# design.net
KiCad netlist of a schematic drawn in Altium Designer
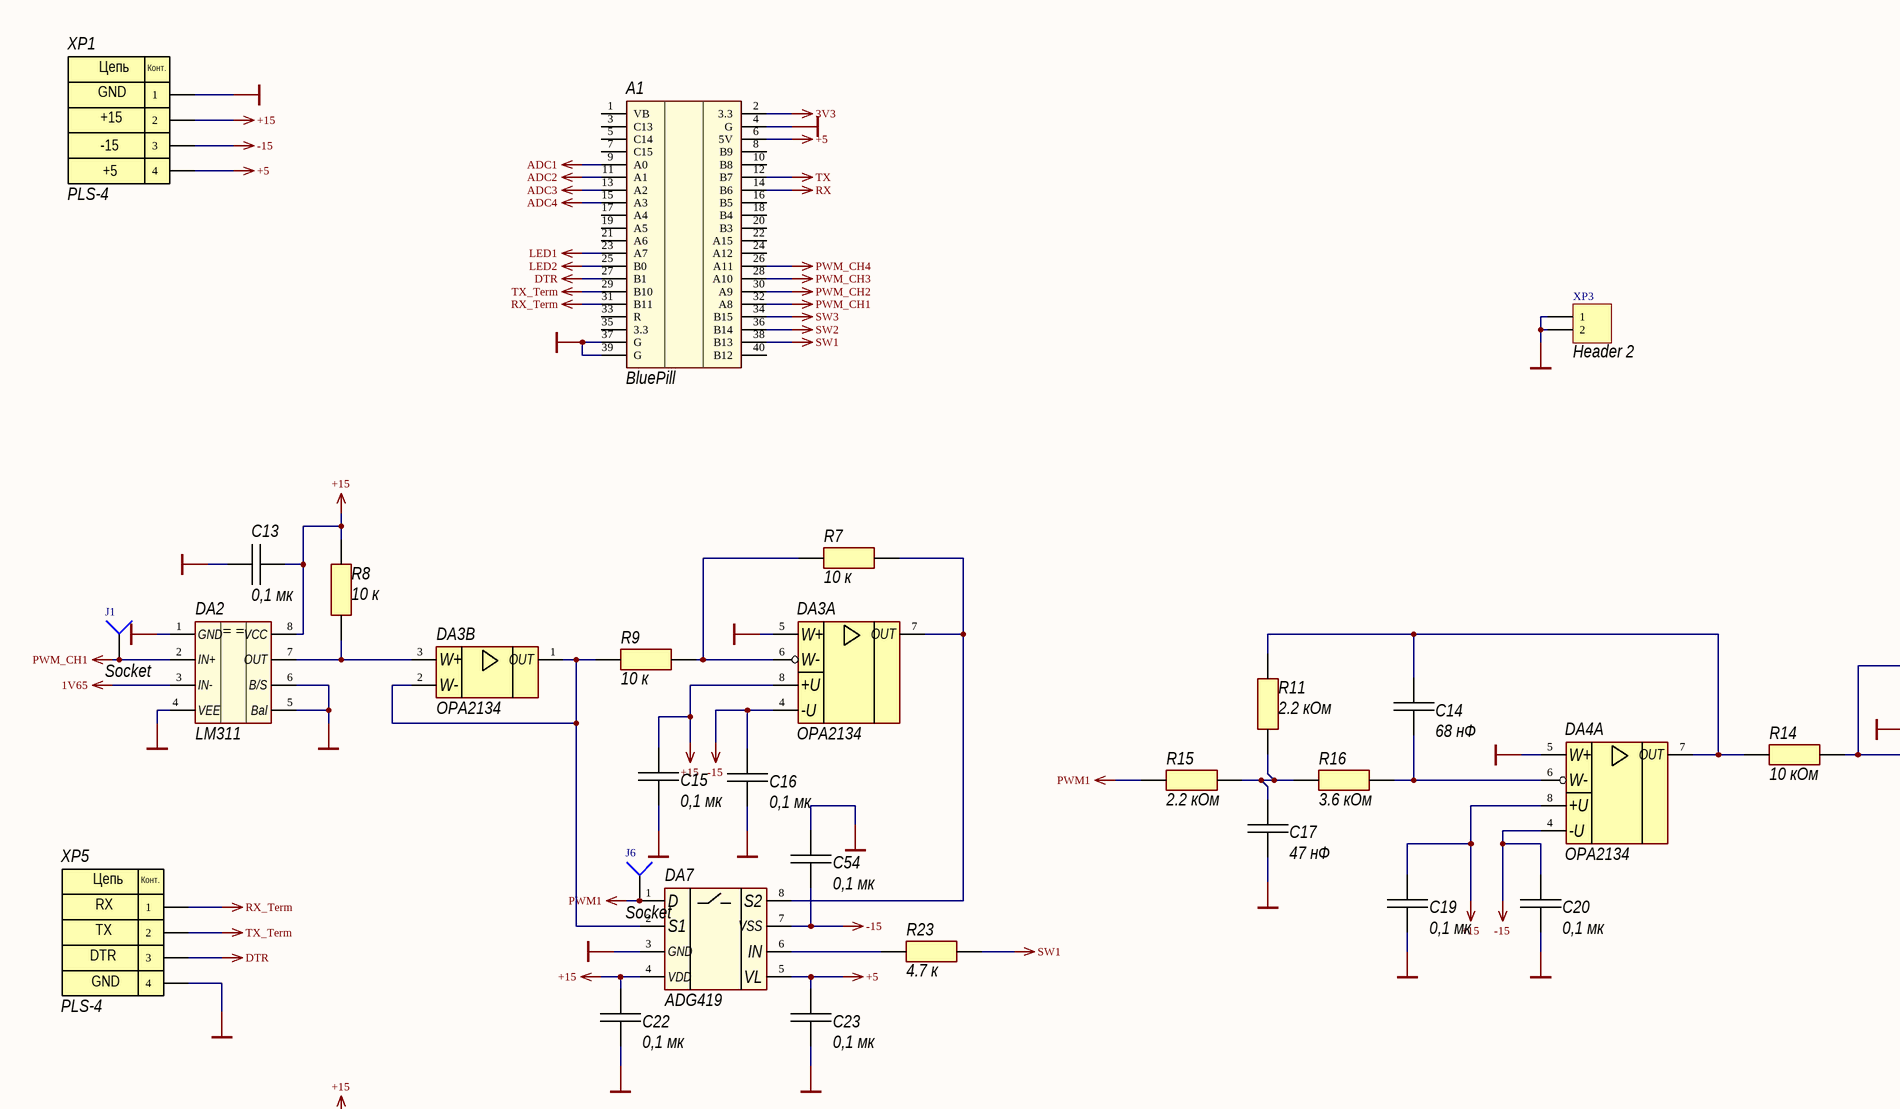
[diagram p0: схема.SchDoc, top left]
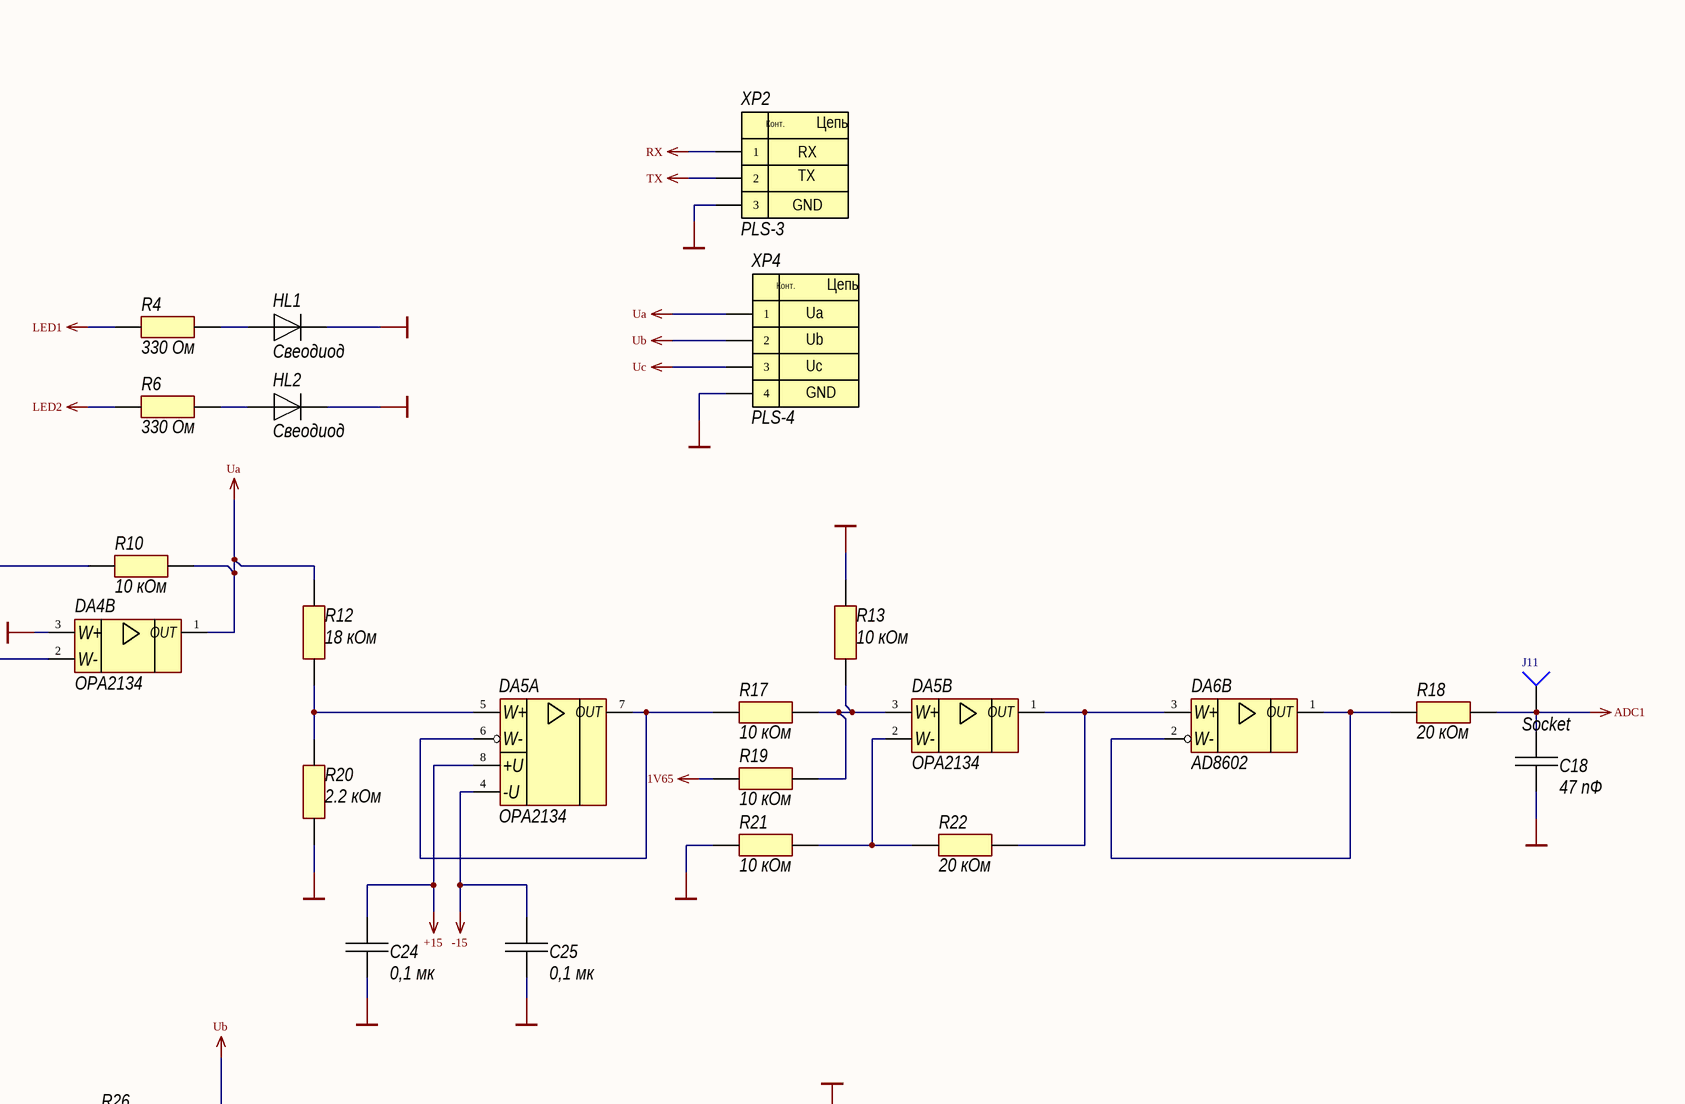
[diagram p1: схема.SchDoc, top right]
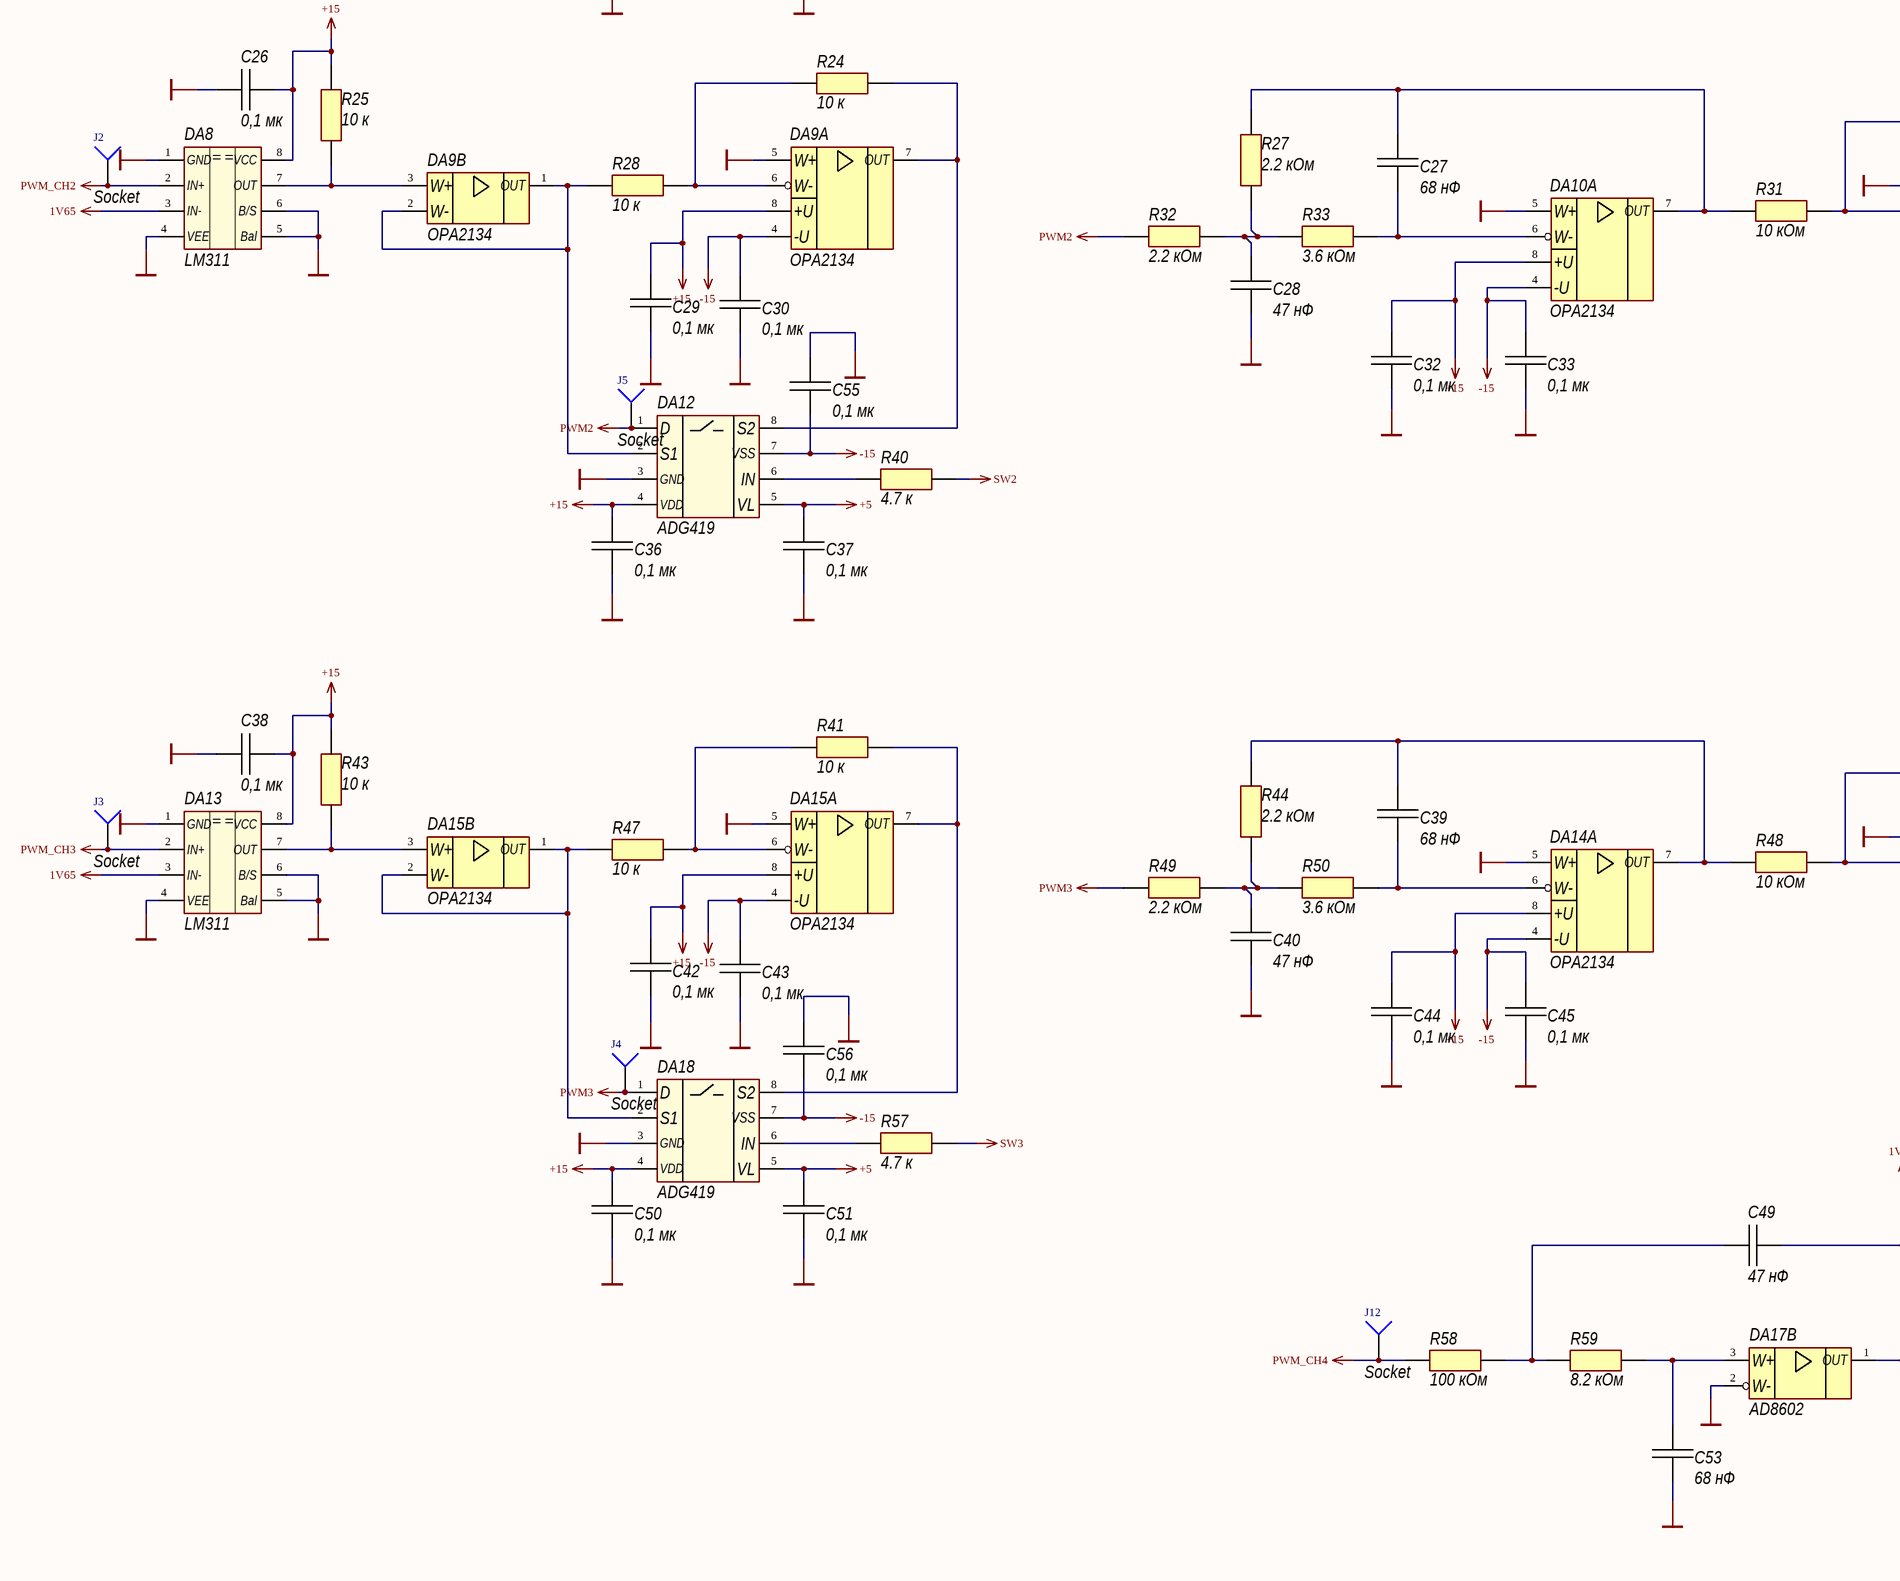
[diagram p2: схема.SchDoc, bottom left]
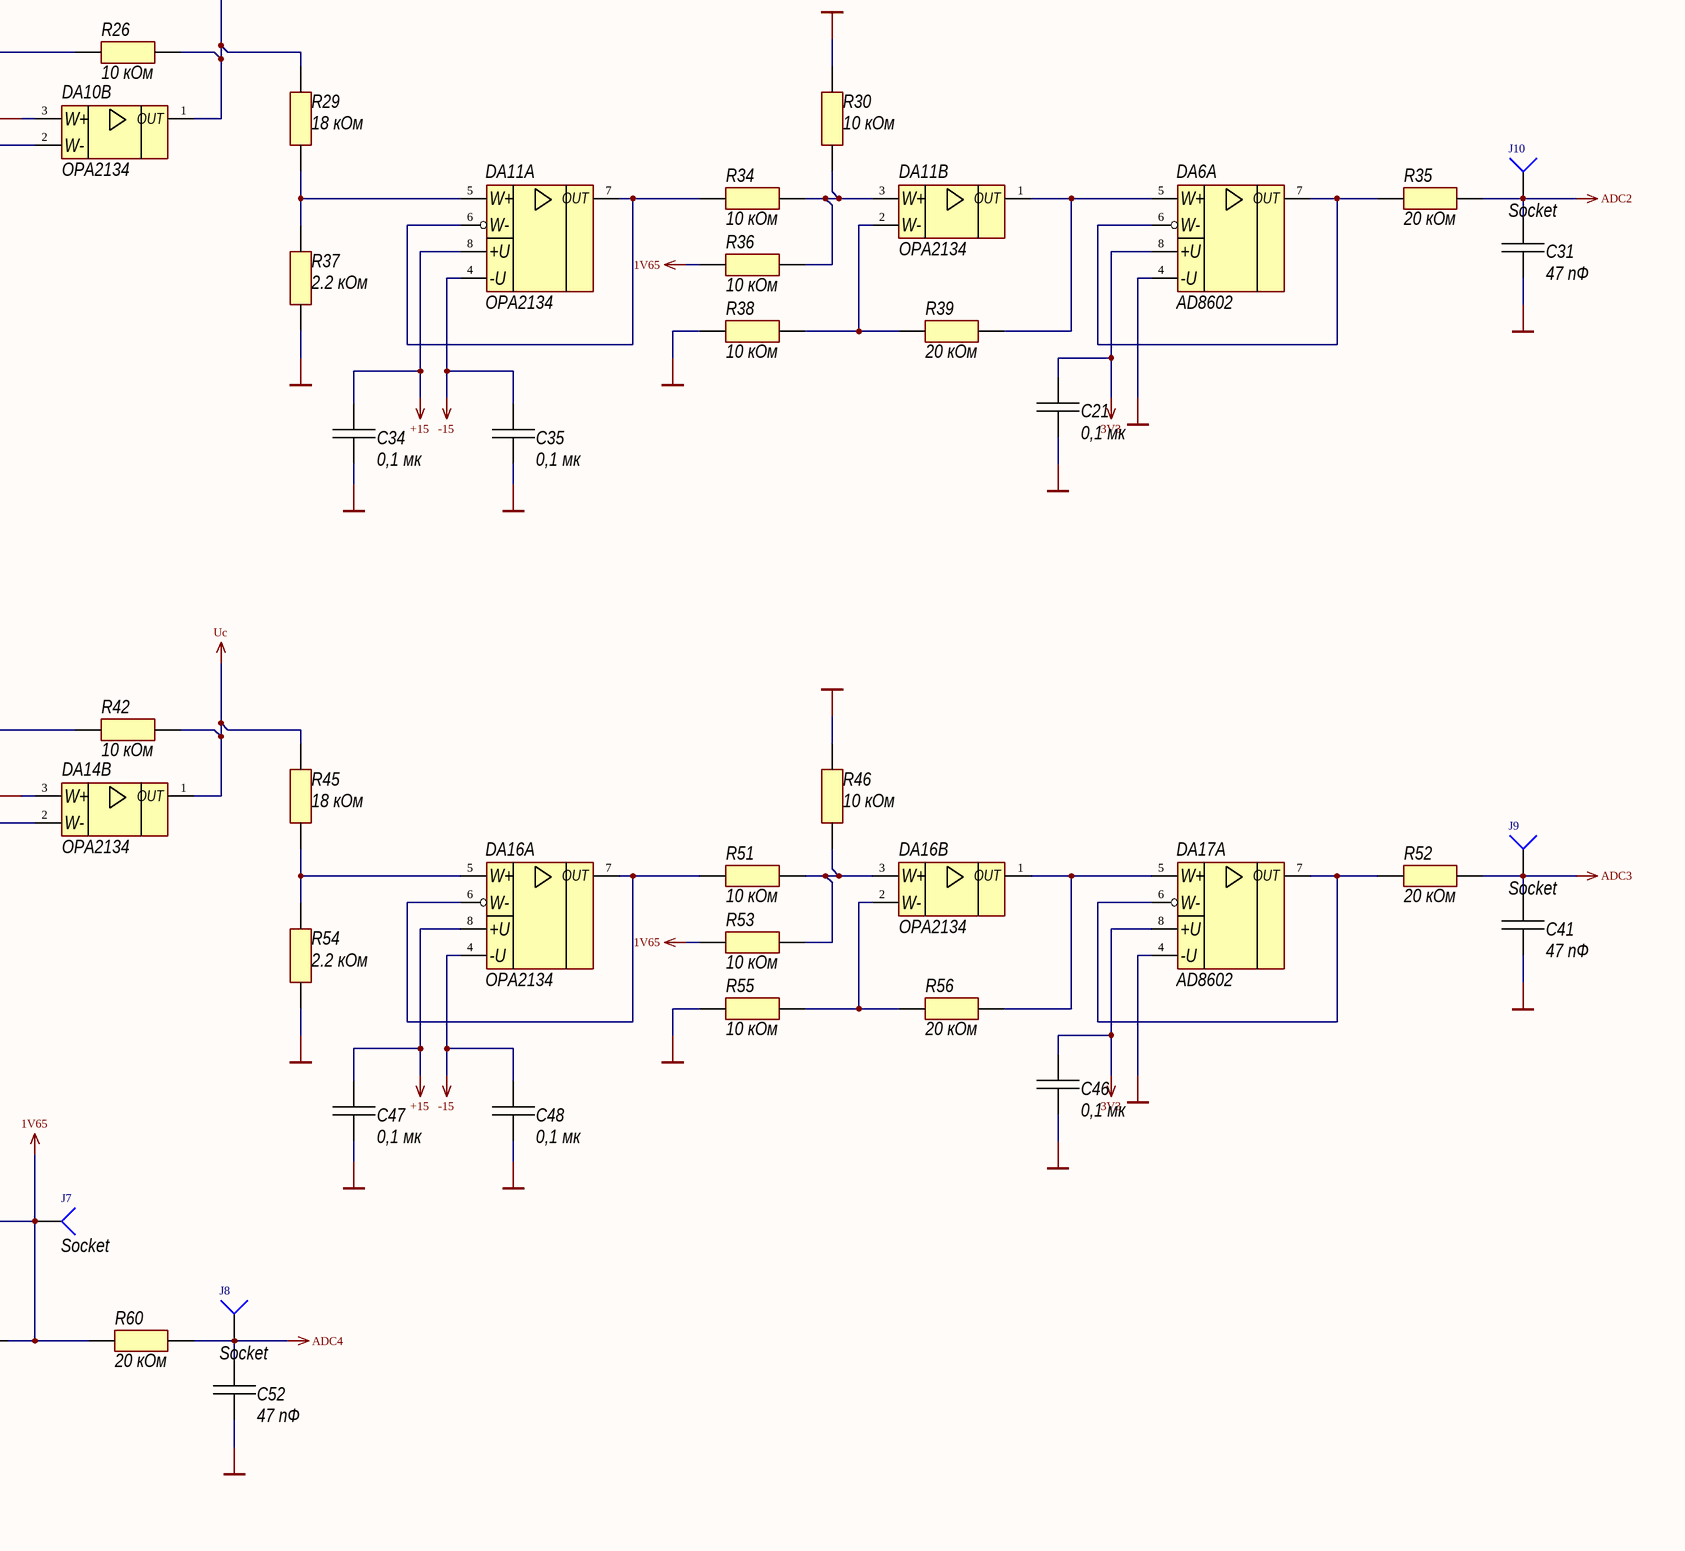
[diagram p3: схема.SchDoc, bottom right]

(export (version "E")
  (design (tool "Eeschema 10.0.6"))
  (components
    (comp (ref "A1") (value "BluePill") (footprint "BluePill") (libsource (lib "Schlib1") (part "BluePill")))
    (comp (ref "C13") (value "0,1 мк") (footprint "CA_0805") (libsource (lib "Schlib1") (part "Конденсатор")))
    (comp (ref "C14") (value "68 нФ") (footprint "CA_0805") (libsource (lib "Schlib1") (part "Конденсатор")))
    (comp (ref "C15") (value "0,1 мк") (footprint "CA_0805") (libsource (lib "Schlib1") (part "Конденсатор")))
    (comp (ref "C16") (value "0,1 мк") (footprint "CA_0805") (libsource (lib "Schlib1") (part "Конденсатор")))
    (comp (ref "C17") (value "47 нФ") (footprint "CA_0805") (libsource (lib "Schlib1") (part "Конденсатор")))
    (comp (ref "C18") (value "47 пФ") (footprint "CA_0805") (libsource (lib "Schlib1") (part "Конденсатор")))
    (comp (ref "C19") (value "0,1 мк") (footprint "CA_0805") (libsource (lib "Schlib1") (part "Конденсатор")))
    (comp (ref "C20") (value "0,1 мк") (footprint "CA_0805") (libsource (lib "Schlib1") (part "Конденсатор")))
    (comp (ref "C21") (value "0,1 мк") (footprint "CA_0805") (libsource (lib "Schlib1") (part "Конденсатор")))
    (comp (ref "C22") (value "0,1 мк") (footprint "CA_0805") (libsource (lib "Schlib1") (part "Конденсатор")))
    (comp (ref "C23") (value "0,1 мк") (footprint "CA_0805") (libsource (lib "Schlib1") (part "Конденсатор")))
    (comp (ref "C24") (value "0,1 мк") (footprint "CA_0805") (libsource (lib "Schlib1") (part "Конденсатор")))
    (comp (ref "C25") (value "0,1 мк") (footprint "CA_0805") (libsource (lib "Schlib1") (part "Конденсатор")))
    (comp (ref "C26") (value "0,1 мк") (footprint "CA_0805") (libsource (lib "Schlib1") (part "Конденсатор")))
    (comp (ref "C27") (value "68 нФ") (footprint "CA_0805") (libsource (lib "Schlib1") (part "Конденсатор")))
    (comp (ref "C28") (value "47 нФ") (footprint "CA_0805") (libsource (lib "Schlib1") (part "Конденсатор")))
    (comp (ref "C29") (value "0,1 мк") (footprint "CA_0805") (libsource (lib "Schlib1") (part "Конденсатор")))
    (comp (ref "C30") (value "0,1 мк") (footprint "CA_0805") (libsource (lib "Schlib1") (part "Конденсатор")))
    (comp (ref "C31") (value "47 пФ") (footprint "CA_0805") (libsource (lib "Schlib1") (part "Конденсатор")))
    (comp (ref "C32") (value "0,1 мк") (footprint "CA_0805") (libsource (lib "Schlib1") (part "Конденсатор")))
    (comp (ref "C33") (value "0,1 мк") (footprint "CA_0805") (libsource (lib "Schlib1") (part "Конденсатор")))
    (comp (ref "C34") (value "0,1 мк") (footprint "CA_0805") (libsource (lib "Schlib1") (part "Конденсатор")))
    (comp (ref "C35") (value "0,1 мк") (footprint "CA_0805") (libsource (lib "Schlib1") (part "Конденсатор")))
    (comp (ref "C36") (value "0,1 мк") (footprint "CA_0805") (libsource (lib "Schlib1") (part "Конденсатор")))
    (comp (ref "C37") (value "0,1 мк") (footprint "CA_0805") (libsource (lib "Schlib1") (part "Конденсатор")))
    (comp (ref "C38") (value "0,1 мк") (footprint "CA_0805") (libsource (lib "Schlib1") (part "Конденсатор")))
    (comp (ref "C39") (value "68 нФ") (footprint "CA_0805") (libsource (lib "Schlib1") (part "Конденсатор")))
    (comp (ref "C40") (value "47 нФ") (footprint "CA_0805") (libsource (lib "Schlib1") (part "Конденсатор")))
    (comp (ref "C41") (value "47 пФ") (footprint "CA_0805") (libsource (lib "Schlib1") (part "Конденсатор")))
    (comp (ref "C42") (value "0,1 мк") (footprint "CA_0805") (libsource (lib "Schlib1") (part "Конденсатор")))
    (comp (ref "C43") (value "0,1 мк") (footprint "CA_0805") (libsource (lib "Schlib1") (part "Конденсатор")))
    (comp (ref "C44") (value "0,1 мк") (footprint "CA_0805") (libsource (lib "Schlib1") (part "Конденсатор")))
    (comp (ref "C45") (value "0,1 мк") (footprint "CA_0805") (libsource (lib "Schlib1") (part "Конденсатор")))
    (comp (ref "C46") (value "0,1 мк") (footprint "CA_0805") (libsource (lib "Schlib1") (part "Конденсатор")))
    (comp (ref "C47") (value "0,1 мк") (footprint "CA_0805") (libsource (lib "Schlib1") (part "Конденсатор")))
    (comp (ref "C48") (value "0,1 мк") (footprint "CA_0805") (libsource (lib "Schlib1") (part "Конденсатор")))
    (comp (ref "C49") (value "47 нФ") (footprint "CA_0805") (libsource (lib "Schlib1") (part "Конденсатор")))
    (comp (ref "C50") (value "0,1 мк") (footprint "CA_0805") (libsource (lib "Schlib1") (part "Конденсатор")))
    (comp (ref "C51") (value "0,1 мк") (footprint "CA_0805") (libsource (lib "Schlib1") (part "Конденсатор")))
    (comp (ref "C52") (value "47 пФ") (footprint "CA_0805") (libsource (lib "Schlib1") (part "Конденсатор")))
    (comp (ref "C53") (value "68 нФ") (footprint "CA_0805") (libsource (lib "Schlib1") (part "Конденсатор")))
    (comp (ref "C54") (value "0,1 мк") (footprint "CA_0805") (libsource (lib "Schlib1") (part "Конденсатор")))
    (comp (ref "C55") (value "0,1 мк") (footprint "CA_0805") (libsource (lib "Schlib1") (part "Конденсатор")))
    (comp (ref "C56") (value "0,1 мк") (footprint "CA_0805") (libsource (lib "Schlib1") (part "Конденсатор")))
    (comp (ref "DA2") (value "LM311") (footprint "SC_SOIC8") (libsource (lib "Schlib1") (part "LM311")))
    (comp (ref "DA3") (value "OPA2134") (footprint "SC_SOIC8") (libsource (lib "Schlib1") (part "OPA2134")))
    (comp (ref "DA4") (value "OPA2134") (footprint "SC_SOIC8") (libsource (lib "Schlib1") (part "OPA2134")))
    (comp (ref "DA5") (value "OPA2134") (footprint "SC_SOIC8") (libsource (lib "Schlib1") (part "OPA2134")))
    (comp (ref "DA6") (value "AD8602") (footprint "SC_SOIC8") (libsource (lib "Schlib1") (part "AD8602")))
    (comp (ref "DA7") (value "ADG419") (footprint "SC_SOIC8") (libsource (lib "Schlib1") (part "ADG419")))
    (comp (ref "DA8") (value "LM311") (footprint "SC_SOIC8") (libsource (lib "Schlib1") (part "LM311")))
    (comp (ref "DA9") (value "OPA2134") (footprint "SC_SOIC8") (libsource (lib "Schlib1") (part "OPA2134")))
    (comp (ref "DA10") (value "OPA2134") (footprint "SC_SOIC8") (libsource (lib "Schlib1") (part "OPA2134")))
    (comp (ref "DA11") (value "OPA2134") (footprint "SC_SOIC8") (libsource (lib "Schlib1") (part "OPA2134")))
    (comp (ref "DA12") (value "ADG419") (footprint "SC_SOIC8") (libsource (lib "Schlib1") (part "ADG419")))
    (comp (ref "DA13") (value "LM311") (footprint "SC_SOIC8") (libsource (lib "Schlib1") (part "LM311")))
    (comp (ref "DA14") (value "OPA2134") (footprint "SC_SOIC8") (libsource (lib "Schlib1") (part "OPA2134")))
    (comp (ref "DA15") (value "OPA2134") (footprint "SC_SOIC8") (libsource (lib "Schlib1") (part "OPA2134")))
    (comp (ref "DA16") (value "OPA2134") (footprint "SC_SOIC8") (libsource (lib "Schlib1") (part "OPA2134")))
    (comp (ref "DA17") (value "AD8602") (footprint "SC_SOIC8") (libsource (lib "Schlib1") (part "AD8602")))
    (comp (ref "DA18") (value "ADG419") (footprint "SC_SOIC8") (libsource (lib "Schlib1") (part "ADG419")))
    (comp (ref "HL1")
      (value "Свеодиод")
      (footprint "DI_LED_0805")
      (libsource (lib "Schlib1") (part "Свеодиод"))
    )
    (comp (ref "HL2")
      (value "Свеодиод")
      (footprint "DI_LED_0805")
      (libsource (lib "Schlib1") (part "Свеодиод"))
    )
    (comp (ref "J1")
      (value "Socket")
      (footprint "PIN1")
      (fields (field (name "PUBLISHER") "Altium Limited"))
      (libsource (lib "Miscellaneous Connectors") (part "Socket"))
    )
    (comp (ref "J2")
      (value "Socket")
      (footprint "PIN1")
      (fields (field (name "PUBLISHER") "Altium Limited"))
      (libsource (lib "Miscellaneous Connectors") (part "Socket"))
    )
    (comp (ref "J3")
      (value "Socket")
      (footprint "PIN1")
      (fields (field (name "PUBLISHER") "Altium Limited"))
      (libsource (lib "Miscellaneous Connectors") (part "Socket"))
    )
    (comp (ref "J4")
      (value "Socket")
      (footprint "PIN1")
      (fields (field (name "PUBLISHER") "Altium Limited"))
      (libsource (lib "Miscellaneous Connectors") (part "Socket"))
    )
    (comp (ref "J5")
      (value "Socket")
      (footprint "PIN1")
      (fields (field (name "PUBLISHER") "Altium Limited"))
      (libsource (lib "Miscellaneous Connectors") (part "Socket"))
    )
    (comp (ref "J6")
      (value "Socket")
      (footprint "PIN1")
      (fields (field (name "PUBLISHER") "Altium Limited"))
      (libsource (lib "Miscellaneous Connectors") (part "Socket"))
    )
    (comp (ref "J7")
      (value "Socket")
      (footprint "PIN1")
      (fields (field (name "PUBLISHER") "Altium Limited"))
      (libsource (lib "Miscellaneous Connectors") (part "Socket"))
    )
    (comp (ref "J8")
      (value "Socket")
      (footprint "PIN1")
      (fields (field (name "PUBLISHER") "Altium Limited"))
      (libsource (lib "Miscellaneous Connectors") (part "Socket"))
    )
    (comp (ref "J9")
      (value "Socket")
      (footprint "PIN1")
      (fields (field (name "PUBLISHER") "Altium Limited"))
      (libsource (lib "Miscellaneous Connectors") (part "Socket"))
    )
    (comp (ref "J10")
      (value "Socket")
      (footprint "PIN1")
      (fields (field (name "PUBLISHER") "Altium Limited"))
      (libsource (lib "Miscellaneous Connectors") (part "Socket"))
    )
    (comp (ref "J11")
      (value "Socket")
      (footprint "PIN1")
      (fields (field (name "PUBLISHER") "Altium Limited"))
      (libsource (lib "Miscellaneous Connectors") (part "Socket"))
    )
    (comp (ref "J12")
      (value "Socket")
      (footprint "PIN1")
      (fields (field (name "PUBLISHER") "Altium Limited"))
      (libsource (lib "Miscellaneous Connectors") (part "Socket"))
    )
    (comp (ref "R4") (value "330 Ом") (footprint "RE_0805") (libsource (lib "Schlib1") (part "Резистор")))
    (comp (ref "R6") (value "330 Ом") (footprint "RE_0805") (libsource (lib "Schlib1") (part "Резистор")))
    (comp (ref "R7") (value "10 к") (footprint "RE_0805") (libsource (lib "Schlib1") (part "Резистор")))
    (comp (ref "R8") (value "10 к") (footprint "RE_0805") (libsource (lib "") (part "Резистор_2")))
    (comp (ref "R9") (value "10 к") (footprint "RE_0805") (libsource (lib "Schlib1") (part "Резистор")))
    (comp (ref "R10") (value "10 кОм") (footprint "RE_0805") (libsource (lib "Schlib1") (part "Резистор")))
    (comp (ref "R11") (value "2.2 кОм") (footprint "RE_0805") (libsource (lib "") (part "Резистор_3")))
    (comp (ref "R12") (value "18 кОм") (footprint "RE_0805") (libsource (lib "") (part "Резистор_3")))
    (comp (ref "R13") (value "10 кОм") (footprint "RE_0805") (libsource (lib "") (part "Резистор_2")))
    (comp (ref "R14") (value "10 кОм") (footprint "RE_0805") (libsource (lib "Schlib1") (part "Резистор")))
    (comp (ref "R15") (value "2.2 кОм") (footprint "RE_0805") (libsource (lib "Schlib1") (part "Резистор")))
    (comp (ref "R16") (value "3.6 кОм") (footprint "RE_0805") (libsource (lib "Schlib1") (part "Резистор")))
    (comp (ref "R17") (value "10 кОм") (footprint "RE_0805") (libsource (lib "") (part "Резистор_1")))
    (comp (ref "R18") (value "20 кОм") (footprint "RE_0805") (libsource (lib "") (part "Резистор_1")))
    (comp (ref "R19") (value "10 кОм") (footprint "RE_0805") (libsource (lib "") (part "Резистор_1")))
    (comp (ref "R20") (value "2.2 кОм") (footprint "RE_0805") (libsource (lib "") (part "Резистор_3")))
    (comp (ref "R21") (value "10 кОм") (footprint "RE_0805") (libsource (lib "") (part "Резистор_1")))
    (comp (ref "R22") (value "20 кОм") (footprint "RE_0805") (libsource (lib "") (part "Резистор_1")))
    (comp (ref "R23") (value "4.7 к") (footprint "RE_0805") (libsource (lib "Schlib1") (part "Резистор")))
    (comp (ref "R24") (value "10 к") (footprint "RE_0805") (libsource (lib "Schlib1") (part "Резистор")))
    (comp (ref "R25") (value "10 к") (footprint "RE_0805") (libsource (lib "") (part "Резистор_2")))
    (comp (ref "R26") (value "10 кОм") (footprint "RE_0805") (libsource (lib "Schlib1") (part "Резистор")))
    (comp (ref "R27") (value "2.2 кОм") (footprint "RE_0805") (libsource (lib "") (part "Резистор_3")))
    (comp (ref "R28") (value "10 к") (footprint "RE_0805") (libsource (lib "Schlib1") (part "Резистор")))
    (comp (ref "R29") (value "18 кОм") (footprint "RE_0805") (libsource (lib "") (part "Резистор_3")))
    (comp (ref "R30") (value "10 кОм") (footprint "RE_0805") (libsource (lib "") (part "Резистор_2")))
    (comp (ref "R31") (value "10 кОм") (footprint "RE_0805") (libsource (lib "Schlib1") (part "Резистор")))
    (comp (ref "R32") (value "2.2 кОм") (footprint "RE_0805") (libsource (lib "Schlib1") (part "Резистор")))
    (comp (ref "R33") (value "3.6 кОм") (footprint "RE_0805") (libsource (lib "Schlib1") (part "Резистор")))
    (comp (ref "R34") (value "10 кОм") (footprint "RE_0805") (libsource (lib "") (part "Резистор_1")))
    (comp (ref "R35") (value "20 кОм") (footprint "RE_0805") (libsource (lib "") (part "Резистор_1")))
    (comp (ref "R36") (value "10 кОм") (footprint "RE_0805") (libsource (lib "") (part "Резистор_1")))
    (comp (ref "R37") (value "2.2 кОм") (footprint "RE_0805") (libsource (lib "") (part "Резистор_3")))
    (comp (ref "R38") (value "10 кОм") (footprint "RE_0805") (libsource (lib "") (part "Резистор_1")))
    (comp (ref "R39") (value "20 кОм") (footprint "RE_0805") (libsource (lib "") (part "Резистор_1")))
    (comp (ref "R40") (value "4.7 к") (footprint "RE_0805") (libsource (lib "Schlib1") (part "Резистор")))
    (comp (ref "R41") (value "10 к") (footprint "RE_0805") (libsource (lib "Schlib1") (part "Резистор")))
    (comp (ref "R42") (value "10 кОм") (footprint "RE_0805") (libsource (lib "Schlib1") (part "Резистор")))
    (comp (ref "R43") (value "10 к") (footprint "RE_0805") (libsource (lib "") (part "Резистор_2")))
    (comp (ref "R44") (value "2.2 кОм") (footprint "RE_0805") (libsource (lib "") (part "Резистор_3")))
    (comp (ref "R45") (value "18 кОм") (footprint "RE_0805") (libsource (lib "") (part "Резистор_3")))
    (comp (ref "R46") (value "10 кОм") (footprint "RE_0805") (libsource (lib "") (part "Резистор_2")))
    (comp (ref "R47") (value "10 к") (footprint "RE_0805") (libsource (lib "Schlib1") (part "Резистор")))
    (comp (ref "R48") (value "10 кОм") (footprint "RE_0805") (libsource (lib "Schlib1") (part "Резистор")))
    (comp (ref "R49") (value "2.2 кОм") (footprint "RE_0805") (libsource (lib "Schlib1") (part "Резистор")))
    (comp (ref "R50") (value "3.6 кОм") (footprint "RE_0805") (libsource (lib "Schlib1") (part "Резистор")))
    (comp (ref "R51") (value "10 кОм") (footprint "RE_0805") (libsource (lib "") (part "Резистор_1")))
    (comp (ref "R52") (value "20 кОм") (footprint "RE_0805") (libsource (lib "") (part "Резистор_1")))
    (comp (ref "R53") (value "10 кОм") (footprint "RE_0805") (libsource (lib "") (part "Резистор_1")))
    (comp (ref "R54") (value "2.2 кОм") (footprint "RE_0805") (libsource (lib "") (part "Резистор_3")))
    (comp (ref "R55") (value "10 кОм") (footprint "RE_0805") (libsource (lib "") (part "Резистор_1")))
    (comp (ref "R56") (value "20 кОм") (footprint "RE_0805") (libsource (lib "") (part "Резистор_1")))
    (comp (ref "R57") (value "4.7 к") (footprint "RE_0805") (libsource (lib "Schlib1") (part "Резистор")))
    (comp (ref "R58") (value "100 кОм") (footprint "RE_0805") (libsource (lib "Schlib1") (part "Резистор")))
    (comp (ref "R59") (value "8.2 кОм") (footprint "RE_0805") (libsource (lib "Schlib1") (part "Резистор")))
    (comp (ref "R60") (value "20 кОм") (footprint "RE_0805") (libsource (lib "") (part "Резистор_1")))
    (comp (ref "XP1") (value "PLS-4") (footprint "PLS4") (libsource (lib "Schlib1") (part "PLS-4")))
    (comp (ref "XP2") (value "PLS-3") (footprint "PLS3") (libsource (lib "Schlib1") (part "PLS-3")))
    (comp (ref "XP3")
      (value "Header 2")
      (footprint "HDR1X2")
      (description "Header, 2-Pin")
      (fields (field (name "PUBLISHER") "Altium Limited"))
      (libsource (lib "Miscellaneous Connectors") (part "Header 2"))
    )
    (comp (ref "XP4") (value "PLS-4") (footprint "PLS4") (libsource (lib "") (part "PLS-4_1")))
    (comp (ref "XP5") (value "PLS-4") (footprint "PLS4") (libsource (lib "Schlib1") (part "PLS-4")))
  )
  (nets
    (net (code "1") (name "+5") (class "Default")
      (node (ref "A1") (pin "6") (pinfunction "5V_6") (pintype "passive"))
      (node (ref "C23") (pin "2") (pinfunction "2_2") (pintype "passive"))
      (node (ref "C37") (pin "2") (pinfunction "2_2") (pintype "passive"))
      (node (ref "C51") (pin "2") (pinfunction "2_2") (pintype "passive"))
      (node (ref "DA12") (pin "5") (pinfunction "VL_5") (pintype "passive"))
      (node (ref "DA18") (pin "5") (pinfunction "VL_5") (pintype "passive"))
      (node (ref "DA7") (pin "5") (pinfunction "VL_5") (pintype "passive"))
      (node (ref "XP1") (pin "4") (pinfunction "4_4") (pintype "passive"))
    )
    (net (code "2") (name "+15") (class "Default")
      (node (ref "C13") (pin "1") (pinfunction "1_1") (pintype "passive"))
      (node (ref "C15") (pin "2") (pinfunction "2_2") (pintype "passive"))
      (node (ref "C19") (pin "2") (pinfunction "2_2") (pintype "passive"))
      (node (ref "C22") (pin "2") (pinfunction "2_2") (pintype "passive"))
      (node (ref "C24") (pin "2") (pinfunction "2_2") (pintype "passive"))
      (node (ref "C26") (pin "1") (pinfunction "1_1") (pintype "passive"))
      (node (ref "C29") (pin "2") (pinfunction "2_2") (pintype "passive"))
      (node (ref "C32") (pin "2") (pinfunction "2_2") (pintype "passive"))
      (node (ref "C34") (pin "2") (pinfunction "2_2") (pintype "passive"))
      (node (ref "C36") (pin "2") (pinfunction "2_2") (pintype "passive"))
      (node (ref "C38") (pin "1") (pinfunction "1_1") (pintype "passive"))
      (node (ref "C42") (pin "2") (pinfunction "2_2") (pintype "passive"))
      (node (ref "C44") (pin "2") (pinfunction "2_2") (pintype "passive"))
      (node (ref "C47") (pin "2") (pinfunction "2_2") (pintype "passive"))
      (node (ref "C50") (pin "2") (pinfunction "2_2") (pintype "passive"))
      (node (ref "DA10") (pin "8") (pinfunction "+U_8") (pintype "passive"))
      (node (ref "DA11") (pin "8") (pinfunction "+U_8") (pintype "passive"))
      (node (ref "DA12") (pin "4") (pinfunction "VDD_4") (pintype "passive"))
      (node (ref "DA13") (pin "8") (pinfunction "VCC_8") (pintype "passive"))
      (node (ref "DA14") (pin "8") (pinfunction "+U_8") (pintype "passive"))
      (node (ref "DA15") (pin "8") (pinfunction "+U_8") (pintype "passive"))
      (node (ref "DA16") (pin "8") (pinfunction "+U_8") (pintype "passive"))
      (node (ref "DA18") (pin "4") (pinfunction "VDD_4") (pintype "passive"))
      (node (ref "DA2") (pin "8") (pinfunction "VCC_8") (pintype "passive"))
      (node (ref "DA3") (pin "8") (pinfunction "+U_8") (pintype "passive"))
      (node (ref "DA4") (pin "8") (pinfunction "+U_8") (pintype "passive"))
      (node (ref "DA5") (pin "8") (pinfunction "+U_8") (pintype "passive"))
      (node (ref "DA7") (pin "4") (pinfunction "VDD_4") (pintype "passive"))
      (node (ref "DA8") (pin "8") (pinfunction "VCC_8") (pintype "passive"))
      (node (ref "DA9") (pin "8") (pinfunction "+U_8") (pintype "passive"))
      (node (ref "R25") (pin "1") (pinfunction "1_1") (pintype "passive"))
      (node (ref "R43") (pin "1") (pinfunction "1_1") (pintype "passive"))
      (node (ref "R8") (pin "1") (pinfunction "1_1") (pintype "passive"))
      (node (ref "XP1") (pin "2") (pinfunction "2_2") (pintype "passive"))
    )
    (net (code "3") (name "-15") (class "Default")
      (node (ref "C16") (pin "2") (pinfunction "2_2") (pintype "passive"))
      (node (ref "C20") (pin "2") (pinfunction "2_2") (pintype "passive"))
      (node (ref "C25") (pin "2") (pinfunction "2_2") (pintype "passive"))
      (node (ref "C30") (pin "2") (pinfunction "2_2") (pintype "passive"))
      (node (ref "C33") (pin "2") (pinfunction "2_2") (pintype "passive"))
      (node (ref "C35") (pin "2") (pinfunction "2_2") (pintype "passive"))
      (node (ref "C43") (pin "2") (pinfunction "2_2") (pintype "passive"))
      (node (ref "C45") (pin "2") (pinfunction "2_2") (pintype "passive"))
      (node (ref "C48") (pin "2") (pinfunction "2_2") (pintype "passive"))
      (node (ref "C54") (pin "1") (pinfunction "1_1") (pintype "passive"))
      (node (ref "C55") (pin "1") (pinfunction "1_1") (pintype "passive"))
      (node (ref "C56") (pin "1") (pinfunction "1_1") (pintype "passive"))
      (node (ref "DA10") (pin "4") (pinfunction "-U_4") (pintype "passive"))
      (node (ref "DA11") (pin "4") (pinfunction "-U_4") (pintype "passive"))
      (node (ref "DA12") (pin "7") (pinfunction "VSS_7") (pintype "passive"))
      (node (ref "DA14") (pin "4") (pinfunction "-U_4") (pintype "passive"))
      (node (ref "DA15") (pin "4") (pinfunction "-U_4") (pintype "passive"))
      (node (ref "DA16") (pin "4") (pinfunction "-U_4") (pintype "passive"))
      (node (ref "DA18") (pin "7") (pinfunction "VSS_7") (pintype "passive"))
      (node (ref "DA3") (pin "4") (pinfunction "-U_4") (pintype "passive"))
      (node (ref "DA4") (pin "4") (pinfunction "-U_4") (pintype "passive"))
      (node (ref "DA5") (pin "4") (pinfunction "-U_4") (pintype "passive"))
      (node (ref "DA7") (pin "7") (pinfunction "VSS_7") (pintype "passive"))
      (node (ref "DA9") (pin "4") (pinfunction "-U_4") (pintype "passive"))
      (node (ref "XP1") (pin "3") (pinfunction "3_3") (pintype "passive"))
    )
    (net (code "4") (name "1V65") (class "Default")
      (node (ref "C49") (pin "2") (pinfunction "2_2") (pintype "passive"))
      (node (ref "DA13") (pin "3") (pinfunction "IN-_3") (pintype "passive"))
      (node (ref "DA17") (pin "1") (pinfunction "OUT_1") (pintype "passive"))
      (node (ref "DA2") (pin "3") (pinfunction "IN-_3") (pintype "passive"))
      (node (ref "DA8") (pin "3") (pinfunction "IN-_3") (pintype "passive"))
      (node (ref "J7") (pin "1") (pinfunction "1_1") (pintype "passive"))
      (node (ref "R19") (pin "2") (pinfunction "2_2") (pintype "passive"))
      (node (ref "R36") (pin "2") (pinfunction "2_2") (pintype "passive"))
      (node (ref "R53") (pin "2") (pinfunction "2_2") (pintype "passive"))
      (node (ref "R60") (pin "2") (pinfunction "2_2") (pintype "passive"))
    )
    (net (code "5") (name "3V3") (class "Default")
      (node (ref "A1") (pin "2") (pinfunction "3.3_2") (pintype "passive"))
      (node (ref "C21") (pin "2") (pinfunction "2_2") (pintype "passive"))
      (node (ref "C46") (pin "2") (pinfunction "2_2") (pintype "passive"))
      (node (ref "DA17") (pin "8") (pinfunction "+U_8") (pintype "passive"))
      (node (ref "DA6") (pin "8") (pinfunction "+U_8") (pintype "passive"))
    )
    (net (code "6") (name "ADC1") (class "Default")
      (node (ref "A1") (pin "9") (pinfunction "A0_9") (pintype "passive"))
      (node (ref "C18") (pin "2") (pinfunction "2_2") (pintype "passive"))
      (node (ref "J11") (pin "1") (pinfunction "1_1") (pintype "passive"))
      (node (ref "R18") (pin "1") (pinfunction "1_1") (pintype "passive"))
    )
    (net (code "7") (name "ADC2") (class "Default")
      (node (ref "A1") (pin "11") (pinfunction "A1_11") (pintype "passive"))
      (node (ref "C31") (pin "2") (pinfunction "2_2") (pintype "passive"))
      (node (ref "J10") (pin "1") (pinfunction "1_1") (pintype "passive"))
      (node (ref "R35") (pin "1") (pinfunction "1_1") (pintype "passive"))
    )
    (net (code "8") (name "ADC3") (class "Default")
      (node (ref "A1") (pin "13") (pinfunction "A2_13") (pintype "passive"))
      (node (ref "C41") (pin "2") (pinfunction "2_2") (pintype "passive"))
      (node (ref "J9") (pin "1") (pinfunction "1_1") (pintype "passive"))
      (node (ref "R52") (pin "1") (pinfunction "1_1") (pintype "passive"))
    )
    (net (code "9") (name "ADC4") (class "Default")
      (node (ref "A1") (pin "15") (pinfunction "A3_15") (pintype "passive"))
      (node (ref "C52") (pin "2") (pinfunction "2_2") (pintype "passive"))
      (node (ref "J8") (pin "1") (pinfunction "1_1") (pintype "passive"))
      (node (ref "R60") (pin "1") (pinfunction "1_1") (pintype "passive"))
    )
    (net (code "10") (name "DTR") (class "Default")
      (node (ref "A1") (pin "27") (pinfunction "B1_27") (pintype "passive"))
      (node (ref "XP5") (pin "3") (pinfunction "3_3") (pintype "passive"))
    )
    (net (code "11") (name "GND") (class "Default")
      (node (ref "A1") (pin "37") (pinfunction "G_37") (pintype "passive"))
      (node (ref "A1") (pin "39") (pinfunction "G_39") (pintype "passive"))
      (node (ref "A1") (pin "4") (pinfunction "G_4") (pintype "passive"))
      (node (ref "C13") (pin "2") (pinfunction "2_2") (pintype "passive"))
      (node (ref "C15") (pin "1") (pinfunction "1_1") (pintype "passive"))
      (node (ref "C16") (pin "1") (pinfunction "1_1") (pintype "passive"))
      (node (ref "C17") (pin "1") (pinfunction "1_1") (pintype "passive"))
      (node (ref "C18") (pin "1") (pinfunction "1_1") (pintype "passive"))
      (node (ref "C19") (pin "1") (pinfunction "1_1") (pintype "passive"))
      (node (ref "C20") (pin "1") (pinfunction "1_1") (pintype "passive"))
      (node (ref "C21") (pin "1") (pinfunction "1_1") (pintype "passive"))
      (node (ref "C22") (pin "1") (pinfunction "1_1") (pintype "passive"))
      (node (ref "C23") (pin "1") (pinfunction "1_1") (pintype "passive"))
      (node (ref "C24") (pin "1") (pinfunction "1_1") (pintype "passive"))
      (node (ref "C25") (pin "1") (pinfunction "1_1") (pintype "passive"))
      (node (ref "C26") (pin "2") (pinfunction "2_2") (pintype "passive"))
      (node (ref "C28") (pin "1") (pinfunction "1_1") (pintype "passive"))
      (node (ref "C29") (pin "1") (pinfunction "1_1") (pintype "passive"))
      (node (ref "C30") (pin "1") (pinfunction "1_1") (pintype "passive"))
      (node (ref "C31") (pin "1") (pinfunction "1_1") (pintype "passive"))
      (node (ref "C32") (pin "1") (pinfunction "1_1") (pintype "passive"))
      (node (ref "C33") (pin "1") (pinfunction "1_1") (pintype "passive"))
      (node (ref "C34") (pin "1") (pinfunction "1_1") (pintype "passive"))
      (node (ref "C35") (pin "1") (pinfunction "1_1") (pintype "passive"))
      (node (ref "C36") (pin "1") (pinfunction "1_1") (pintype "passive"))
      (node (ref "C37") (pin "1") (pinfunction "1_1") (pintype "passive"))
      (node (ref "C38") (pin "2") (pinfunction "2_2") (pintype "passive"))
      (node (ref "C40") (pin "1") (pinfunction "1_1") (pintype "passive"))
      (node (ref "C41") (pin "1") (pinfunction "1_1") (pintype "passive"))
      (node (ref "C42") (pin "1") (pinfunction "1_1") (pintype "passive"))
      (node (ref "C43") (pin "1") (pinfunction "1_1") (pintype "passive"))
      (node (ref "C44") (pin "1") (pinfunction "1_1") (pintype "passive"))
      (node (ref "C45") (pin "1") (pinfunction "1_1") (pintype "passive"))
      (node (ref "C46") (pin "1") (pinfunction "1_1") (pintype "passive"))
      (node (ref "C47") (pin "1") (pinfunction "1_1") (pintype "passive"))
      (node (ref "C48") (pin "1") (pinfunction "1_1") (pintype "passive"))
      (node (ref "C50") (pin "1") (pinfunction "1_1") (pintype "passive"))
      (node (ref "C51") (pin "1") (pinfunction "1_1") (pintype "passive"))
      (node (ref "C52") (pin "1") (pinfunction "1_1") (pintype "passive"))
      (node (ref "C53") (pin "2") (pinfunction "2_2") (pintype "passive"))
      (node (ref "C54") (pin "2") (pinfunction "2_2") (pintype "passive"))
      (node (ref "C55") (pin "2") (pinfunction "2_2") (pintype "passive"))
      (node (ref "C56") (pin "2") (pinfunction "2_2") (pintype "passive"))
      (node (ref "DA10") (pin "3") (pinfunction "W+_3") (pintype "passive"))
      (node (ref "DA10") (pin "5") (pinfunction "W+_5") (pintype "passive"))
      (node (ref "DA12") (pin "3") (pinfunction "GND_3") (pintype "passive"))
      (node (ref "DA13") (pin "1") (pinfunction "GND_1") (pintype "passive"))
      (node (ref "DA13") (pin "4") (pinfunction "VEE_4") (pintype "passive"))
      (node (ref "DA13") (pin "5") (pinfunction "Bal_5") (pintype "passive"))
      (node (ref "DA13") (pin "6") (pinfunction "B/S_6") (pintype "passive"))
      (node (ref "DA14") (pin "3") (pinfunction "W+_3") (pintype "passive"))
      (node (ref "DA14") (pin "5") (pinfunction "W+_5") (pintype "passive"))
      (node (ref "DA15") (pin "5") (pinfunction "W+_5") (pintype "passive"))
      (node (ref "DA17") (pin "2") (pinfunction "W-_2") (pintype "passive"))
      (node (ref "DA17") (pin "4") (pinfunction "-U_4") (pintype "passive"))
      (node (ref "DA18") (pin "3") (pinfunction "GND_3") (pintype "passive"))
      (node (ref "DA2") (pin "1") (pinfunction "GND_1") (pintype "passive"))
      (node (ref "DA2") (pin "4") (pinfunction "VEE_4") (pintype "passive"))
      (node (ref "DA2") (pin "5") (pinfunction "Bal_5") (pintype "passive"))
      (node (ref "DA2") (pin "6") (pinfunction "B/S_6") (pintype "passive"))
      (node (ref "DA3") (pin "5") (pinfunction "W+_5") (pintype "passive"))
      (node (ref "DA4") (pin "3") (pinfunction "W+_3") (pintype "passive"))
      (node (ref "DA4") (pin "5") (pinfunction "W+_5") (pintype "passive"))
      (node (ref "DA6") (pin "4") (pinfunction "-U_4") (pintype "passive"))
      (node (ref "DA7") (pin "3") (pinfunction "GND_3") (pintype "passive"))
      (node (ref "DA8") (pin "1") (pinfunction "GND_1") (pintype "passive"))
      (node (ref "DA8") (pin "4") (pinfunction "VEE_4") (pintype "passive"))
      (node (ref "DA8") (pin "5") (pinfunction "Bal_5") (pintype "passive"))
      (node (ref "DA8") (pin "6") (pinfunction "B/S_6") (pintype "passive"))
      (node (ref "DA9") (pin "5") (pinfunction "W+_5") (pintype "passive"))
      (node (ref "HL1") (pin "2") (pinfunction "2_2") (pintype "passive"))
      (node (ref "HL2") (pin "2") (pinfunction "2_2") (pintype "passive"))
      (node (ref "R13") (pin "1") (pinfunction "1_1") (pintype "passive"))
      (node (ref "R20") (pin "1") (pinfunction "1_1") (pintype "passive"))
      (node (ref "R21") (pin "2") (pinfunction "2_2") (pintype "passive"))
      (node (ref "R30") (pin "1") (pinfunction "1_1") (pintype "passive"))
      (node (ref "R37") (pin "1") (pinfunction "1_1") (pintype "passive"))
      (node (ref "R38") (pin "2") (pinfunction "2_2") (pintype "passive"))
      (node (ref "R46") (pin "1") (pinfunction "1_1") (pintype "passive"))
      (node (ref "R54") (pin "1") (pinfunction "1_1") (pintype "passive"))
      (node (ref "R55") (pin "2") (pinfunction "2_2") (pintype "passive"))
      (node (ref "XP1") (pin "1") (pinfunction "1_1") (pintype "passive"))
      (node (ref "XP2") (pin "3") (pinfunction "3_3") (pintype "passive"))
      (node (ref "XP3") (pin "1") (pinfunction "1_1") (pintype "passive"))
      (node (ref "XP3") (pin "2") (pinfunction "2_2") (pintype "passive"))
      (node (ref "XP4") (pin "4") (pinfunction "4_4") (pintype "passive"))
      (node (ref "XP5") (pin "4") (pinfunction "4_4") (pintype "passive"))
    )
    (net (code "12") (name "LED1") (class "Default")
      (node (ref "A1") (pin "23") (pinfunction "A7_23") (pintype "passive"))
      (node (ref "R4") (pin "1") (pinfunction "1_1") (pintype "passive"))
    )
    (net (code "13") (name "LED2") (class "Default")
      (node (ref "A1") (pin "25") (pinfunction "B0_25") (pintype "passive"))
      (node (ref "R6") (pin "1") (pinfunction "1_1") (pintype "passive"))
    )
    (net (code "14") (name "Net-(C17-Pad2)") (class "Default")
      (node (ref "C17") (pin "2") (pinfunction "2_2") (pintype "passive"))
      (node (ref "R11") (pin "1") (pinfunction "1_1") (pintype "passive"))
      (node (ref "R15") (pin "2") (pinfunction "2_2") (pintype "passive"))
      (node (ref "R16") (pin "1") (pinfunction "1_1") (pintype "passive"))
    )
    (net (code "15") (name "Net-(C28-Pad2)") (class "Default")
      (node (ref "C28") (pin "2") (pinfunction "2_2") (pintype "passive"))
      (node (ref "R27") (pin "1") (pinfunction "1_1") (pintype "passive"))
      (node (ref "R32") (pin "2") (pinfunction "2_2") (pintype "passive"))
      (node (ref "R33") (pin "1") (pinfunction "1_1") (pintype "passive"))
    )
    (net (code "16") (name "Net-(C40-Pad2)") (class "Default")
      (node (ref "C40") (pin "2") (pinfunction "2_2") (pintype "passive"))
      (node (ref "R44") (pin "1") (pinfunction "1_1") (pintype "passive"))
      (node (ref "R49") (pin "2") (pinfunction "2_2") (pintype "passive"))
      (node (ref "R50") (pin "1") (pinfunction "1_1") (pintype "passive"))
    )
    (net (code "17") (name "Net-(C49-Pad1)") (class "Default")
      (node (ref "C49") (pin "1") (pinfunction "1_1") (pintype "passive"))
      (node (ref "R58") (pin "2") (pinfunction "2_2") (pintype "passive"))
      (node (ref "R59") (pin "1") (pinfunction "1_1") (pintype "passive"))
    )
    (net (code "18") (name "Net-(DA2-OUT)") (class "Default")
      (node (ref "DA2") (pin "7") (pinfunction "OUT_7") (pintype "passive"))
      (node (ref "DA3") (pin "3") (pinfunction "W+_3") (pintype "passive"))
      (node (ref "R8") (pin "2") (pinfunction "2_2") (pintype "passive"))
    )
    (net (code "19") (name "Net-(DA3A-OUT)") (class "Default")
      (node (ref "DA3") (pin "7") (pinfunction "OUT_7") (pintype "passive"))
      (node (ref "DA7") (pin "8") (pinfunction "S2_8") (pintype "passive"))
      (node (ref "R7") (pin "2") (pinfunction "2_2") (pintype "passive"))
    )
    (net (code "20") (name "Net-(DA3A-W-)") (class "Default")
      (node (ref "DA3") (pin "6") (pinfunction "W-_6") (pintype "passive"))
      (node (ref "R7") (pin "1") (pinfunction "1_1") (pintype "passive"))
      (node (ref "R9") (pin "2") (pinfunction "2_2") (pintype "passive"))
    )
    (net (code "21") (name "Net-(DA3B-OUT)") (class "Default")
      (node (ref "DA3") (pin "1") (pinfunction "OUT_1") (pintype "passive"))
      (node (ref "DA3") (pin "2") (pinfunction "W-_2") (pintype "passive"))
      (node (ref "DA7") (pin "2") (pinfunction "S1_2") (pintype "passive"))
      (node (ref "R9") (pin "1") (pinfunction "1_1") (pintype "passive"))
    )
    (net (code "22") (name "Net-(DA4A-OUT)") (class "Default")
      (node (ref "C14") (pin "2") (pinfunction "2_2") (pintype "passive"))
      (node (ref "DA4") (pin "7") (pinfunction "OUT_7") (pintype "passive"))
      (node (ref "R11") (pin "2") (pinfunction "2_2") (pintype "passive"))
      (node (ref "R14") (pin "1") (pinfunction "1_1") (pintype "passive"))
    )
    (net (code "23") (name "Net-(DA4A-W-)") (class "Default")
      (node (ref "C14") (pin "1") (pinfunction "1_1") (pintype "passive"))
      (node (ref "DA4") (pin "6") (pinfunction "W-_6") (pintype "passive"))
      (node (ref "R16") (pin "2") (pinfunction "2_2") (pintype "passive"))
    )
    (net (code "24") (name "Net-(DA4B-W-)") (class "Default")
      (node (ref "DA4") (pin "2") (pinfunction "W-_2") (pintype "passive"))
      (node (ref "R10") (pin "1") (pinfunction "1_1") (pintype "passive"))
      (node (ref "R14") (pin "2") (pinfunction "2_2") (pintype "passive"))
    )
    (net (code "25") (name "Net-(DA5A-OUT)") (class "Default")
      (node (ref "DA5") (pin "6") (pinfunction "W-_6") (pintype "passive"))
      (node (ref "DA5") (pin "7") (pinfunction "OUT_7") (pintype "passive"))
      (node (ref "R17") (pin "2") (pinfunction "2_2") (pintype "passive"))
    )
    (net (code "26") (name "Net-(DA5A-W+)") (class "Default")
      (node (ref "DA5") (pin "5") (pinfunction "W+_5") (pintype "passive"))
      (node (ref "R12") (pin "1") (pinfunction "1_1") (pintype "passive"))
      (node (ref "R20") (pin "2") (pinfunction "2_2") (pintype "passive"))
    )
    (net (code "27") (name "Net-(DA5B-OUT)") (class "Default")
      (node (ref "DA5") (pin "1") (pinfunction "OUT_1") (pintype "passive"))
      (node (ref "DA6") (pin "3") (pinfunction "W+_3") (pintype "passive"))
      (node (ref "R22") (pin "1") (pinfunction "1_1") (pintype "passive"))
    )
    (net (code "28") (name "Net-(DA5B-W+)") (class "Default")
      (node (ref "DA5") (pin "3") (pinfunction "W+_3") (pintype "passive"))
      (node (ref "R13") (pin "2") (pinfunction "2_2") (pintype "passive"))
      (node (ref "R17") (pin "1") (pinfunction "1_1") (pintype "passive"))
      (node (ref "R19") (pin "1") (pinfunction "1_1") (pintype "passive"))
    )
    (net (code "29") (name "Net-(DA5B-W-)") (class "Default")
      (node (ref "DA5") (pin "2") (pinfunction "W-_2") (pintype "passive"))
      (node (ref "R21") (pin "1") (pinfunction "1_1") (pintype "passive"))
      (node (ref "R22") (pin "2") (pinfunction "2_2") (pintype "passive"))
    )
    (net (code "30") (name "Net-(DA6A-OUT)") (class "Default")
      (node (ref "DA6") (pin "6") (pinfunction "W-_6") (pintype "passive"))
      (node (ref "DA6") (pin "7") (pinfunction "OUT_7") (pintype "passive"))
      (node (ref "R35") (pin "2") (pinfunction "2_2") (pintype "passive"))
    )
    (net (code "31") (name "Net-(DA6B-OUT)") (class "Default")
      (node (ref "DA6") (pin "1") (pinfunction "OUT_1") (pintype "passive"))
      (node (ref "DA6") (pin "2") (pinfunction "W-_2") (pintype "passive"))
      (node (ref "R18") (pin "2") (pinfunction "2_2") (pintype "passive"))
    )
    (net (code "32") (name "Net-(DA7-IN)") (class "Default")
      (node (ref "DA7") (pin "6") (pinfunction "IN_6") (pintype "passive"))
      (node (ref "R23") (pin "1") (pinfunction "1_1") (pintype "passive"))
    )
    (net (code "33") (name "Net-(DA8-OUT)") (class "Default")
      (node (ref "DA8") (pin "7") (pinfunction "OUT_7") (pintype "passive"))
      (node (ref "DA9") (pin "3") (pinfunction "W+_3") (pintype "passive"))
      (node (ref "R25") (pin "2") (pinfunction "2_2") (pintype "passive"))
    )
    (net (code "34") (name "Net-(DA9A-W-)") (class "Default")
      (node (ref "DA9") (pin "6") (pinfunction "W-_6") (pintype "passive"))
      (node (ref "R24") (pin "1") (pinfunction "1_1") (pintype "passive"))
      (node (ref "R28") (pin "2") (pinfunction "2_2") (pintype "passive"))
    )
    (net (code "35") (name "Net-(DA10A-OUT)") (class "Default")
      (node (ref "C27") (pin "2") (pinfunction "2_2") (pintype "passive"))
      (node (ref "DA10") (pin "7") (pinfunction "OUT_7") (pintype "passive"))
      (node (ref "R27") (pin "2") (pinfunction "2_2") (pintype "passive"))
      (node (ref "R31") (pin "1") (pinfunction "1_1") (pintype "passive"))
    )
    (net (code "36") (name "Net-(DA10A-W-)") (class "Default")
      (node (ref "C27") (pin "1") (pinfunction "1_1") (pintype "passive"))
      (node (ref "DA10") (pin "6") (pinfunction "W-_6") (pintype "passive"))
      (node (ref "R33") (pin "2") (pinfunction "2_2") (pintype "passive"))
    )
    (net (code "37") (name "Net-(DA10B-W-)") (class "Default")
      (node (ref "DA10") (pin "2") (pinfunction "W-_2") (pintype "passive"))
      (node (ref "R26") (pin "1") (pinfunction "1_1") (pintype "passive"))
      (node (ref "R31") (pin "2") (pinfunction "2_2") (pintype "passive"))
    )
    (net (code "38") (name "Net-(DA11A-OUT)") (class "Default")
      (node (ref "DA11") (pin "6") (pinfunction "W-_6") (pintype "passive"))
      (node (ref "DA11") (pin "7") (pinfunction "OUT_7") (pintype "passive"))
      (node (ref "R34") (pin "2") (pinfunction "2_2") (pintype "passive"))
    )
    (net (code "39") (name "Net-(DA11A-W+)") (class "Default")
      (node (ref "DA11") (pin "5") (pinfunction "W+_5") (pintype "passive"))
      (node (ref "R29") (pin "1") (pinfunction "1_1") (pintype "passive"))
      (node (ref "R37") (pin "2") (pinfunction "2_2") (pintype "passive"))
    )
    (net (code "40") (name "Net-(DA11B-OUT)") (class "Default")
      (node (ref "DA11") (pin "1") (pinfunction "OUT_1") (pintype "passive"))
      (node (ref "DA6") (pin "5") (pinfunction "W+_5") (pintype "passive"))
      (node (ref "R39") (pin "1") (pinfunction "1_1") (pintype "passive"))
    )
    (net (code "41") (name "Net-(DA11B-W+)") (class "Default")
      (node (ref "DA11") (pin "3") (pinfunction "W+_3") (pintype "passive"))
      (node (ref "R30") (pin "2") (pinfunction "2_2") (pintype "passive"))
      (node (ref "R34") (pin "1") (pinfunction "1_1") (pintype "passive"))
      (node (ref "R36") (pin "1") (pinfunction "1_1") (pintype "passive"))
    )
    (net (code "42") (name "Net-(DA11B-W-)") (class "Default")
      (node (ref "DA11") (pin "2") (pinfunction "W-_2") (pintype "passive"))
      (node (ref "R38") (pin "1") (pinfunction "1_1") (pintype "passive"))
      (node (ref "R39") (pin "2") (pinfunction "2_2") (pintype "passive"))
    )
    (net (code "43") (name "Net-(DA12-IN)") (class "Default")
      (node (ref "DA12") (pin "6") (pinfunction "IN_6") (pintype "passive"))
      (node (ref "R40") (pin "1") (pinfunction "1_1") (pintype "passive"))
    )
    (net (code "44") (name "Net-(DA12-S1)") (class "Default")
      (node (ref "DA12") (pin "2") (pinfunction "S1_2") (pintype "passive"))
      (node (ref "DA9") (pin "1") (pinfunction "OUT_1") (pintype "passive"))
      (node (ref "DA9") (pin "2") (pinfunction "W-_2") (pintype "passive"))
      (node (ref "R28") (pin "1") (pinfunction "1_1") (pintype "passive"))
    )
    (net (code "45") (name "Net-(DA12-S2)") (class "Default")
      (node (ref "DA12") (pin "8") (pinfunction "S2_8") (pintype "passive"))
      (node (ref "DA9") (pin "7") (pinfunction "OUT_7") (pintype "passive"))
      (node (ref "R24") (pin "2") (pinfunction "2_2") (pintype "passive"))
    )
    (net (code "46") (name "Net-(DA13-OUT)") (class "Default")
      (node (ref "DA13") (pin "7") (pinfunction "OUT_7") (pintype "passive"))
      (node (ref "DA15") (pin "3") (pinfunction "W+_3") (pintype "passive"))
      (node (ref "R43") (pin "2") (pinfunction "2_2") (pintype "passive"))
    )
    (net (code "47") (name "Net-(DA14A-OUT)") (class "Default")
      (node (ref "C39") (pin "2") (pinfunction "2_2") (pintype "passive"))
      (node (ref "DA14") (pin "7") (pinfunction "OUT_7") (pintype "passive"))
      (node (ref "R44") (pin "2") (pinfunction "2_2") (pintype "passive"))
      (node (ref "R48") (pin "1") (pinfunction "1_1") (pintype "passive"))
    )
    (net (code "48") (name "Net-(DA14A-W-)") (class "Default")
      (node (ref "C39") (pin "1") (pinfunction "1_1") (pintype "passive"))
      (node (ref "DA14") (pin "6") (pinfunction "W-_6") (pintype "passive"))
      (node (ref "R50") (pin "2") (pinfunction "2_2") (pintype "passive"))
    )
    (net (code "49") (name "Net-(DA14B-W-)") (class "Default")
      (node (ref "DA14") (pin "2") (pinfunction "W-_2") (pintype "passive"))
      (node (ref "R42") (pin "1") (pinfunction "1_1") (pintype "passive"))
      (node (ref "R48") (pin "2") (pinfunction "2_2") (pintype "passive"))
    )
    (net (code "50") (name "Net-(DA15A-OUT)") (class "Default")
      (node (ref "DA15") (pin "7") (pinfunction "OUT_7") (pintype "passive"))
      (node (ref "DA18") (pin "8") (pinfunction "S2_8") (pintype "passive"))
      (node (ref "R41") (pin "2") (pinfunction "2_2") (pintype "passive"))
    )
    (net (code "51") (name "Net-(DA15A-W-)") (class "Default")
      (node (ref "DA15") (pin "6") (pinfunction "W-_6") (pintype "passive"))
      (node (ref "R41") (pin "1") (pinfunction "1_1") (pintype "passive"))
      (node (ref "R47") (pin "2") (pinfunction "2_2") (pintype "passive"))
    )
    (net (code "52") (name "Net-(DA15B-OUT)") (class "Default")
      (node (ref "DA15") (pin "1") (pinfunction "OUT_1") (pintype "passive"))
      (node (ref "DA15") (pin "2") (pinfunction "W-_2") (pintype "passive"))
      (node (ref "DA18") (pin "2") (pinfunction "S1_2") (pintype "passive"))
      (node (ref "R47") (pin "1") (pinfunction "1_1") (pintype "passive"))
    )
    (net (code "53") (name "Net-(DA16A-OUT)") (class "Default")
      (node (ref "DA16") (pin "6") (pinfunction "W-_6") (pintype "passive"))
      (node (ref "DA16") (pin "7") (pinfunction "OUT_7") (pintype "passive"))
      (node (ref "R51") (pin "2") (pinfunction "2_2") (pintype "passive"))
    )
    (net (code "54") (name "Net-(DA16A-W+)") (class "Default")
      (node (ref "DA16") (pin "5") (pinfunction "W+_5") (pintype "passive"))
      (node (ref "R45") (pin "1") (pinfunction "1_1") (pintype "passive"))
      (node (ref "R54") (pin "2") (pinfunction "2_2") (pintype "passive"))
    )
    (net (code "55") (name "Net-(DA16B-OUT)") (class "Default")
      (node (ref "DA16") (pin "1") (pinfunction "OUT_1") (pintype "passive"))
      (node (ref "DA17") (pin "5") (pinfunction "W+_5") (pintype "passive"))
      (node (ref "R56") (pin "1") (pinfunction "1_1") (pintype "passive"))
    )
    (net (code "56") (name "Net-(DA16B-W+)") (class "Default")
      (node (ref "DA16") (pin "3") (pinfunction "W+_3") (pintype "passive"))
      (node (ref "R46") (pin "2") (pinfunction "2_2") (pintype "passive"))
      (node (ref "R51") (pin "1") (pinfunction "1_1") (pintype "passive"))
      (node (ref "R53") (pin "1") (pinfunction "1_1") (pintype "passive"))
    )
    (net (code "57") (name "Net-(DA16B-W-)") (class "Default")
      (node (ref "DA16") (pin "2") (pinfunction "W-_2") (pintype "passive"))
      (node (ref "R55") (pin "1") (pinfunction "1_1") (pintype "passive"))
      (node (ref "R56") (pin "2") (pinfunction "2_2") (pintype "passive"))
    )
    (net (code "58") (name "Net-(DA17A-OUT)") (class "Default")
      (node (ref "DA17") (pin "6") (pinfunction "W-_6") (pintype "passive"))
      (node (ref "DA17") (pin "7") (pinfunction "OUT_7") (pintype "passive"))
      (node (ref "R52") (pin "2") (pinfunction "2_2") (pintype "passive"))
    )
    (net (code "59") (name "Net-(DA17B-W+)") (class "Default")
      (node (ref "C53") (pin "1") (pinfunction "1_1") (pintype "passive"))
      (node (ref "DA17") (pin "3") (pinfunction "W+_3") (pintype "passive"))
      (node (ref "R59") (pin "2") (pinfunction "2_2") (pintype "passive"))
    )
    (net (code "60") (name "Net-(DA18-IN)") (class "Default")
      (node (ref "DA18") (pin "6") (pinfunction "IN_6") (pintype "passive"))
      (node (ref "R57") (pin "1") (pinfunction "1_1") (pintype "passive"))
    )
    (net (code "61") (name "Net-(HL1-Pad1)") (class "Default")
      (node (ref "HL1") (pin "1") (pinfunction "1_1") (pintype "passive"))
      (node (ref "R4") (pin "2") (pinfunction "2_2") (pintype "passive"))
    )
    (net (code "62") (name "Net-(HL2-Pad1)") (class "Default")
      (node (ref "HL2") (pin "1") (pinfunction "1_1") (pintype "passive"))
      (node (ref "R6") (pin "2") (pinfunction "2_2") (pintype "passive"))
    )
    (net (code "63") (name "PWM1") (class "Default")
      (node (ref "DA7") (pin "1") (pinfunction "D_1") (pintype "passive"))
      (node (ref "J6") (pin "1") (pinfunction "1_1") (pintype "passive"))
      (node (ref "R15") (pin "1") (pinfunction "1_1") (pintype "passive"))
    )
    (net (code "64") (name "PWM2") (class "Default")
      (node (ref "DA12") (pin "1") (pinfunction "D_1") (pintype "passive"))
      (node (ref "J5") (pin "1") (pinfunction "1_1") (pintype "passive"))
      (node (ref "R32") (pin "1") (pinfunction "1_1") (pintype "passive"))
    )
    (net (code "65") (name "PWM3") (class "Default")
      (node (ref "DA18") (pin "1") (pinfunction "D_1") (pintype "passive"))
      (node (ref "J4") (pin "1") (pinfunction "1_1") (pintype "passive"))
      (node (ref "R49") (pin "1") (pinfunction "1_1") (pintype "passive"))
    )
    (net (code "66") (name "PWM_CH1") (class "Default")
      (node (ref "A1") (pin "32") (pinfunction "A8_32") (pintype "passive"))
      (node (ref "DA2") (pin "2") (pinfunction "IN+_2") (pintype "passive"))
      (node (ref "J1") (pin "1") (pinfunction "1_1") (pintype "passive"))
    )
    (net (code "67") (name "PWM_CH2") (class "Default")
      (node (ref "A1") (pin "30") (pinfunction "A9_30") (pintype "passive"))
      (node (ref "DA8") (pin "2") (pinfunction "IN+_2") (pintype "passive"))
      (node (ref "J2") (pin "1") (pinfunction "1_1") (pintype "passive"))
    )
    (net (code "68") (name "PWM_CH3") (class "Default")
      (node (ref "A1") (pin "28") (pinfunction "A10_28") (pintype "passive"))
      (node (ref "DA13") (pin "2") (pinfunction "IN+_2") (pintype "passive"))
      (node (ref "J3") (pin "1") (pinfunction "1_1") (pintype "passive"))
    )
    (net (code "69") (name "PWM_CH4") (class "Default")
      (node (ref "A1") (pin "26") (pinfunction "A11_26") (pintype "passive"))
      (node (ref "J12") (pin "1") (pinfunction "1_1") (pintype "passive"))
      (node (ref "R58") (pin "1") (pinfunction "1_1") (pintype "passive"))
    )
    (net (code "70") (name "RX") (class "Default")
      (node (ref "A1") (pin "14") (pinfunction "B6_14") (pintype "passive"))
      (node (ref "XP2") (pin "1") (pinfunction "1_1") (pintype "passive"))
    )
    (net (code "71") (name "RX_Term") (class "Default")
      (node (ref "A1") (pin "31") (pinfunction "B11_31") (pintype "passive"))
      (node (ref "XP5") (pin "1") (pinfunction "1_1") (pintype "passive"))
    )
    (net (code "72") (name "SW1") (class "Default")
      (node (ref "A1") (pin "38") (pinfunction "B13_38") (pintype "passive"))
      (node (ref "R23") (pin "2") (pinfunction "2_2") (pintype "passive"))
    )
    (net (code "73") (name "SW2") (class "Default")
      (node (ref "A1") (pin "36") (pinfunction "B14_36") (pintype "passive"))
      (node (ref "R40") (pin "2") (pinfunction "2_2") (pintype "passive"))
    )
    (net (code "74") (name "SW3") (class "Default")
      (node (ref "A1") (pin "34") (pinfunction "B15_34") (pintype "passive"))
      (node (ref "R57") (pin "2") (pinfunction "2_2") (pintype "passive"))
    )
    (net (code "75") (name "TX") (class "Default")
      (node (ref "A1") (pin "12") (pinfunction "B7_12") (pintype "passive"))
      (node (ref "XP2") (pin "2") (pinfunction "2_2") (pintype "passive"))
    )
    (net (code "76") (name "TX_Term") (class "Default")
      (node (ref "A1") (pin "29") (pinfunction "B10_29") (pintype "passive"))
      (node (ref "XP5") (pin "2") (pinfunction "2_2") (pintype "passive"))
    )
    (net (code "77") (name "Ua") (class "Default")
      (node (ref "DA4") (pin "1") (pinfunction "OUT_1") (pintype "passive"))
      (node (ref "R10") (pin "2") (pinfunction "2_2") (pintype "passive"))
      (node (ref "R12") (pin "2") (pinfunction "2_2") (pintype "passive"))
      (node (ref "XP4") (pin "1") (pinfunction "1_1") (pintype "passive"))
    )
    (net (code "78") (name "Ub") (class "Default")
      (node (ref "DA10") (pin "1") (pinfunction "OUT_1") (pintype "passive"))
      (node (ref "R26") (pin "2") (pinfunction "2_2") (pintype "passive"))
      (node (ref "R29") (pin "2") (pinfunction "2_2") (pintype "passive"))
      (node (ref "XP4") (pin "2") (pinfunction "2_2") (pintype "passive"))
    )
    (net (code "79") (name "Uc") (class "Default")
      (node (ref "DA14") (pin "1") (pinfunction "OUT_1") (pintype "passive"))
      (node (ref "R42") (pin "2") (pinfunction "2_2") (pintype "passive"))
      (node (ref "R45") (pin "2") (pinfunction "2_2") (pintype "passive"))
      (node (ref "XP4") (pin "3") (pinfunction "3_3") (pintype "passive"))
    )
    (net (code "80") (name "unconnected-(A1-3.3-Pad35)") (class "Default")
      (node (ref "A1") (pin "35") (pinfunction "3.3_35") (pintype "passive"))
    )
    (net (code "81") (name "unconnected-(A1-A4-Pad17)") (class "Default")
      (node (ref "A1") (pin "17") (pinfunction "A4_17") (pintype "passive"))
    )
    (net (code "82") (name "unconnected-(A1-A5-Pad19)") (class "Default")
      (node (ref "A1") (pin "19") (pinfunction "A5_19") (pintype "passive"))
    )
    (net (code "83") (name "unconnected-(A1-A6-Pad21)") (class "Default")
      (node (ref "A1") (pin "21") (pinfunction "A6_21") (pintype "passive"))
    )
    (net (code "84") (name "unconnected-(A1-A12-Pad24)") (class "Default")
      (node (ref "A1") (pin "24") (pinfunction "A12_24") (pintype "passive"))
    )
    (net (code "85") (name "unconnected-(A1-A15-Pad22)") (class "Default")
      (node (ref "A1") (pin "22") (pinfunction "A15_22") (pintype "passive"))
    )
    (net (code "86") (name "unconnected-(A1-B3-Pad20)") (class "Default")
      (node (ref "A1") (pin "20") (pinfunction "B3_20") (pintype "passive"))
    )
    (net (code "87") (name "unconnected-(A1-B4-Pad18)") (class "Default")
      (node (ref "A1") (pin "18") (pinfunction "B4_18") (pintype "passive"))
    )
    (net (code "88") (name "unconnected-(A1-B5-Pad16)") (class "Default")
      (node (ref "A1") (pin "16") (pinfunction "B5_16") (pintype "passive"))
    )
    (net (code "89") (name "unconnected-(A1-B8-Pad10)") (class "Default")
      (node (ref "A1") (pin "10") (pinfunction "B8_10") (pintype "passive"))
    )
    (net (code "90") (name "unconnected-(A1-B9-Pad8)") (class "Default")
      (node (ref "A1") (pin "8") (pinfunction "B9_8") (pintype "passive"))
    )
    (net (code "91") (name "unconnected-(A1-B12-Pad40)") (class "Default")
      (node (ref "A1") (pin "40") (pinfunction "B12_40") (pintype "passive"))
    )
    (net (code "92") (name "unconnected-(A1-C13-Pad3)") (class "Default")
      (node (ref "A1") (pin "3") (pinfunction "C13_3") (pintype "passive"))
    )
    (net (code "93") (name "unconnected-(A1-C14-Pad5)") (class "Default")
      (node (ref "A1") (pin "5") (pinfunction "C14_5") (pintype "passive"))
    )
    (net (code "94") (name "unconnected-(A1-C15-Pad7)") (class "Default")
      (node (ref "A1") (pin "7") (pinfunction "C15_7") (pintype "passive"))
    )
    (net (code "95") (name "unconnected-(A1-R-Pad33)") (class "Default")
      (node (ref "A1") (pin "33") (pinfunction "R_33") (pintype "passive"))
    )
    (net (code "96") (name "unconnected-(A1-VB-Pad1)") (class "Default")
      (node (ref "A1") (pin "1") (pinfunction "VB_1") (pintype "passive"))
    )
  )
)
